# motor.net
KiCad netlist of a schematic drawn in EAGLE
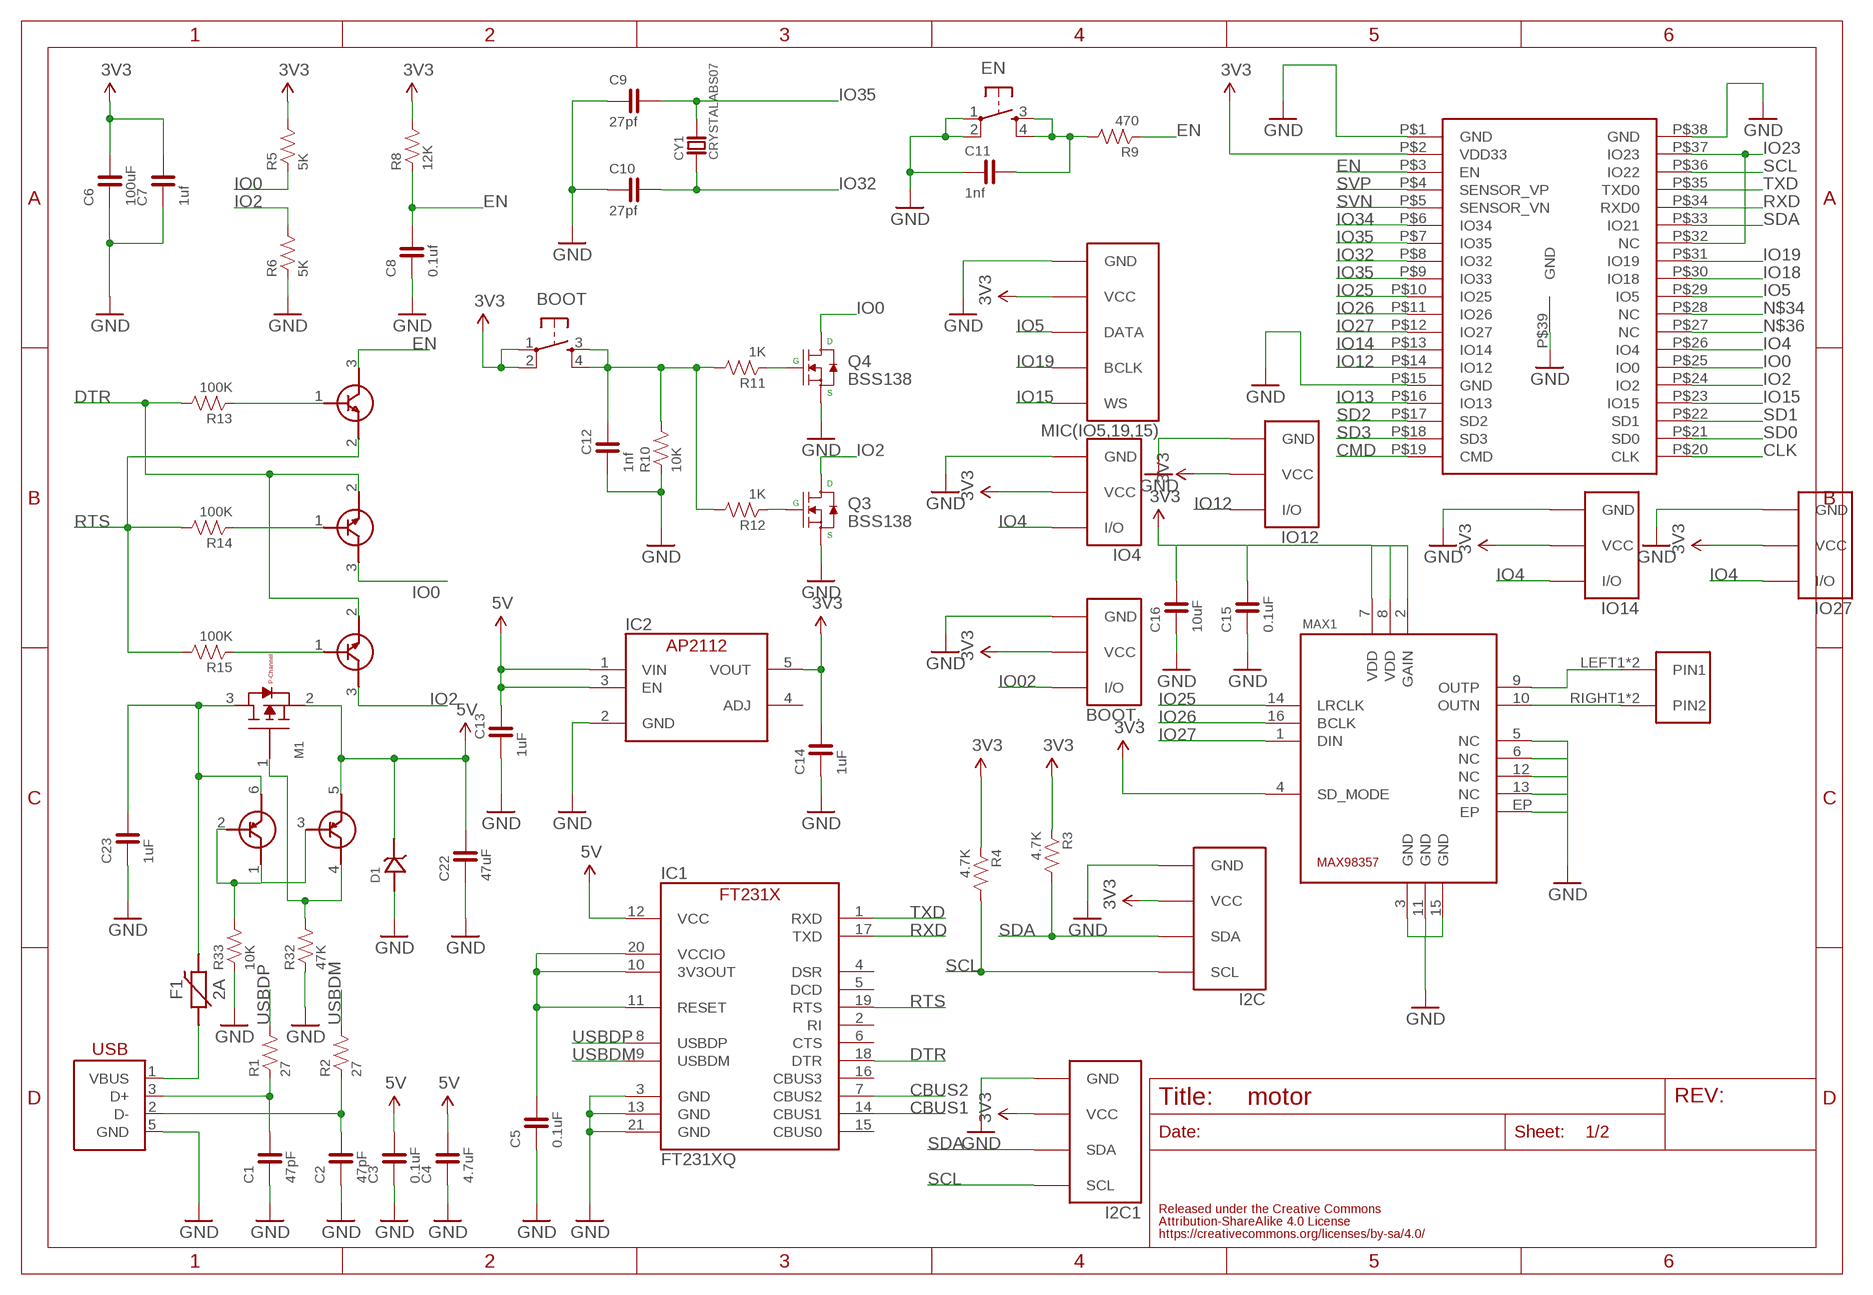
[diagram p0: schematic, sheet 1]
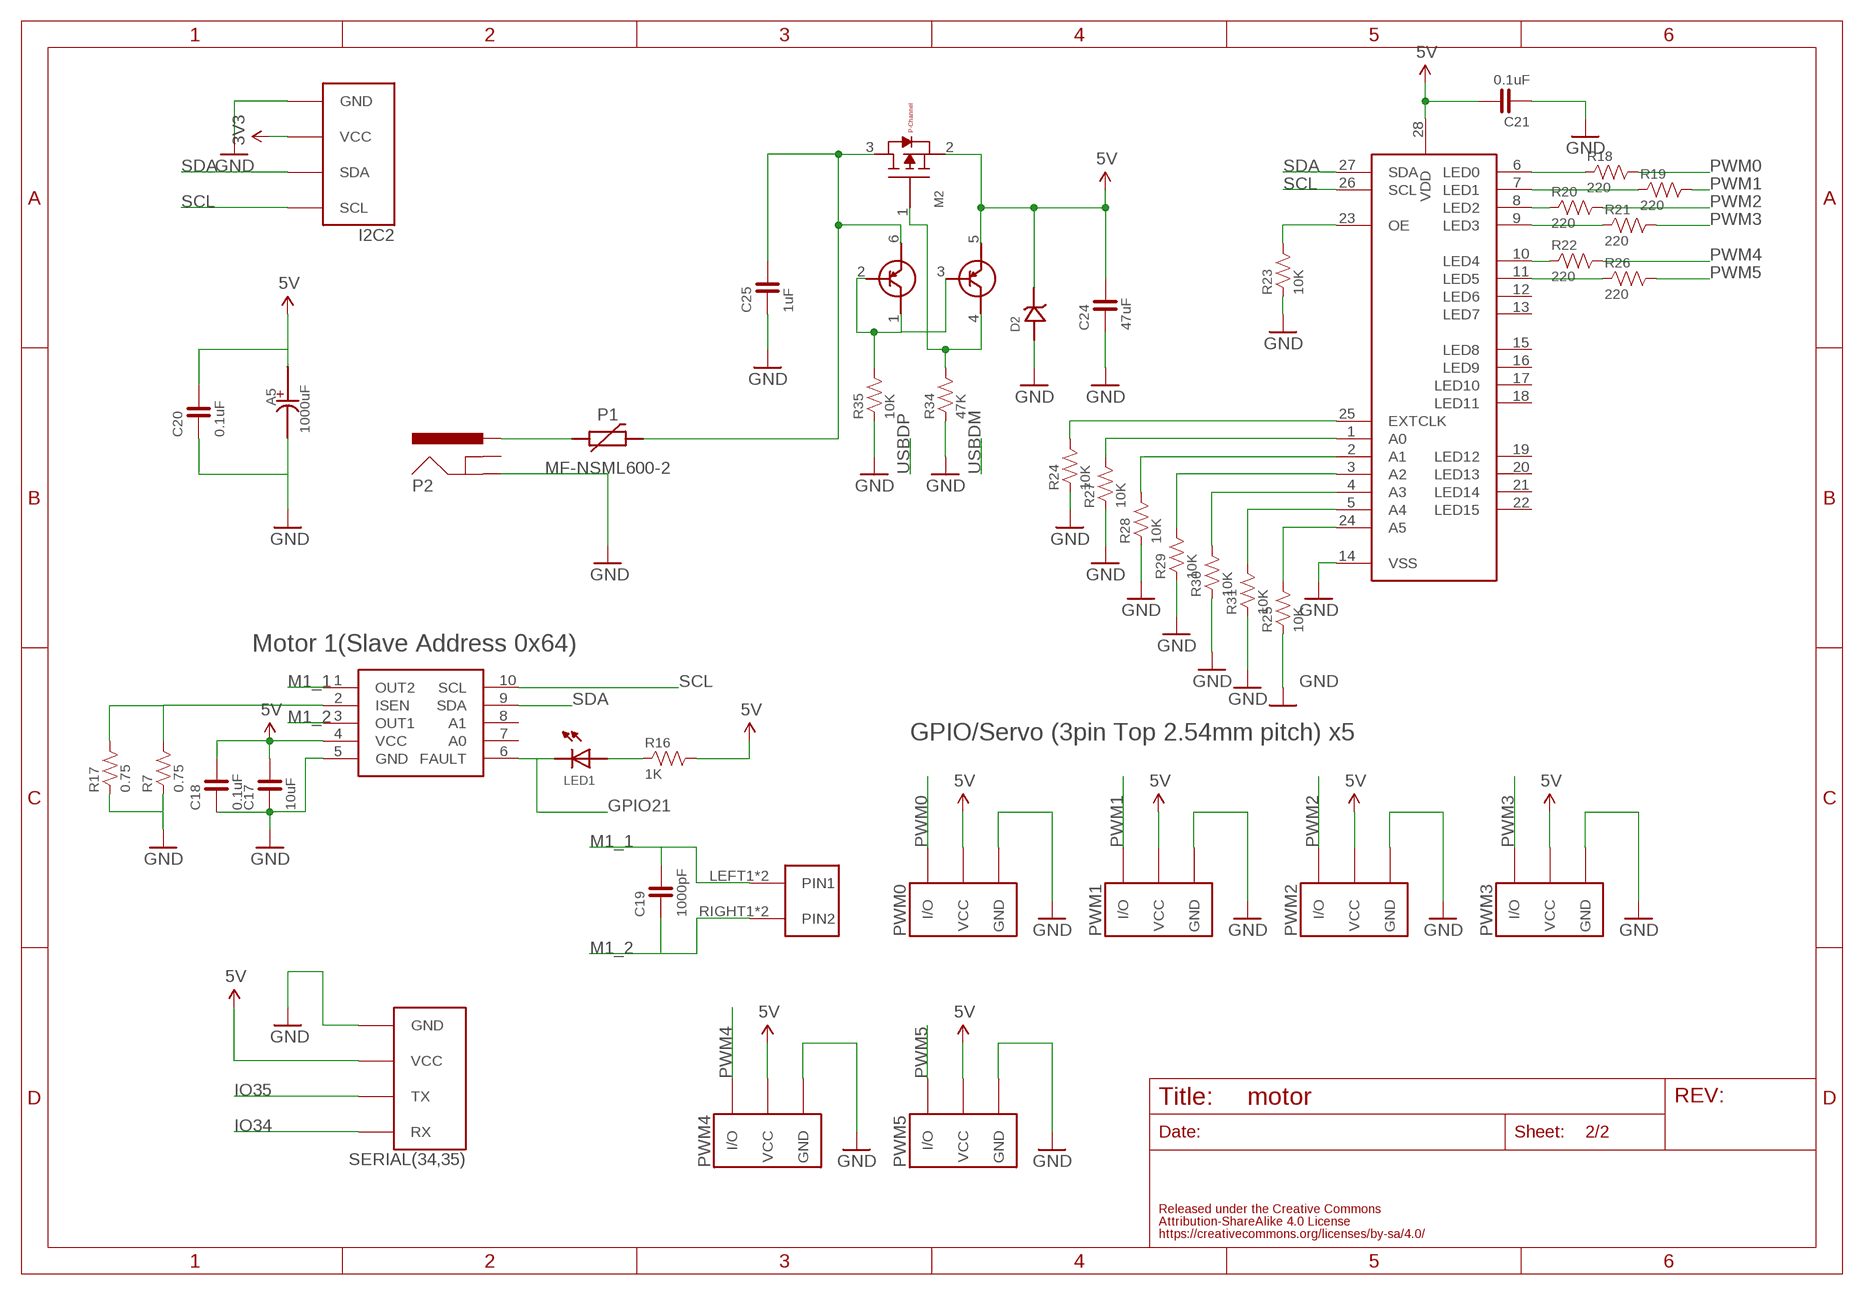
[diagram p1: schematic, sheet 2]

(export (version "E")
  (design (tool "Eeschema 10.0.6"))
  (components
    (comp (ref "A5")
      (value "1000uF")
      (footprint "eagle-import:D12.5")
      (libsource (lib "eagle-import") (part "CAPACITOR-ALUMIN_D12_5"))
    )
    (comp (ref "C17")
      (value "10uF")
      (footprint "eagle-import:0603")
      (libsource (lib "eagle-import") (part "CAPACITOR-0603"))
    )
    (comp (ref "C18")
      (value "0.1uF")
      (footprint "eagle-import:0603")
      (libsource (lib "eagle-import") (part "CAPACITOR-0603"))
    )
    (comp (ref "C19")
      (value "1000pF")
      (footprint "eagle-import:0603")
      (libsource (lib "eagle-import") (part "CAPACITOR-0603"))
    )
    (comp (ref "C20")
      (value "0.1uF")
      (footprint "eagle-import:0603")
      (libsource (lib "eagle-import") (part "CAPACITOR-0603"))
    )
    (comp (ref "C21")
      (value "0.1uF")
      (footprint "eagle-import:0603")
      (libsource (lib "eagle-import") (part "CAPACITOR-0603"))
    )
    (comp (ref "C24")
      (value "47uF")
      (footprint "eagle-import:0603-NARROW")
      (libsource (lib "eagle-import") (part "CAPACITOR-0603_NARROW"))
    )
    (comp (ref "C25")
      (value "1uF")
      (footprint "eagle-import:0603-NARROW")
      (libsource (lib "eagle-import") (part "CAPACITOR-0603_NARROW"))
    )
    (comp (ref "D2")
      (value "SMBJ5.0")
      (footprint "eagle-import:SMBJ5.0")
      (libsource (lib "eagle-import") (part "SMBJ5.0"))
    )
    (comp (ref "I2C2")
      (value "FABO_BRICK_I2C-B04B-PASK-1")
      (footprint "eagle-import:FABO_BRICK_I2C_B04B-PASK-1")
      (libsource (lib "eagle-import") (part "FABO_BRICK_I2C-B04B-PASK-1"))
    )
    (comp (ref "LED1")
      (value "LED-0603")
      (footprint "eagle-import:0603")
      (libsource (lib "eagle-import") (part "LED-0603"))
    )
    (comp (ref "M2")
      (value "MOSFET-P_DMG2305UX")
      (footprint "eagle-import:SOT-23")
      (libsource (lib "eagle-import") (part "MOSFET-P_DMG2305UX"))
    )
    (comp (ref "P1")
      (value "MF-NSML600-2")
      (footprint "eagle-import:1206")
      (libsource (lib "eagle-import") (part "POLYSWITCH1206"))
    )
    (comp (ref "P2")
      (value "DC-JACKM04339A0")
      (footprint "eagle-import:M04339A0")
      (libsource (lib "eagle-import") (part "DC-JACKM04339A0"))
    )
    (comp (ref "PWM0")
      (value "FABO_BRICK_3PIN-HEADER")
      (footprint "eagle-import:FABO_BRICK_3PIN_HEADER")
      (libsource (lib "eagle-import") (part "FABO_BRICK_3PIN-HEADER"))
    )
    (comp (ref "PWM1")
      (value "FABO_BRICK_3PIN-HEADER")
      (footprint "eagle-import:FABO_BRICK_3PIN_HEADER")
      (libsource (lib "eagle-import") (part "FABO_BRICK_3PIN-HEADER"))
    )
    (comp (ref "PWM2")
      (value "FABO_BRICK_3PIN-HEADER")
      (footprint "eagle-import:FABO_BRICK_3PIN_HEADER")
      (libsource (lib "eagle-import") (part "FABO_BRICK_3PIN-HEADER"))
    )
    (comp (ref "PWM3")
      (value "FABO_BRICK_3PIN-HEADER")
      (footprint "eagle-import:FABO_BRICK_3PIN_HEADER")
      (libsource (lib "eagle-import") (part "FABO_BRICK_3PIN-HEADER"))
    )
    (comp (ref "PWM4")
      (value "FABO_BRICK_3PIN-HEADER")
      (footprint "eagle-import:FABO_BRICK_3PIN_HEADER")
      (libsource (lib "eagle-import") (part "FABO_BRICK_3PIN-HEADER"))
    )
    (comp (ref "PWM5")
      (value "FABO_BRICK_3PIN-HEADER")
      (footprint "eagle-import:FABO_BRICK_3PIN_HEADER")
      (libsource (lib "eagle-import") (part "FABO_BRICK_3PIN-HEADER"))
    )
    (comp (ref "R7")
      (value "0.75")
      (footprint "eagle-import:0603")
      (libsource (lib "eagle-import") (part "RESISTOR-0603"))
    )
    (comp (ref "R16")
      (value "1K")
      (footprint "eagle-import:0603")
      (libsource (lib "eagle-import") (part "RESISTOR-0603"))
    )
    (comp (ref "R17")
      (value "0.75")
      (footprint "eagle-import:0603")
      (libsource (lib "eagle-import") (part "RESISTOR-0603"))
    )
    (comp (ref "R18")
      (value "220")
      (footprint "eagle-import:0603")
      (libsource (lib "eagle-import") (part "RESISTOR-0603"))
    )
    (comp (ref "R19")
      (value "220")
      (footprint "eagle-import:0603")
      (libsource (lib "eagle-import") (part "RESISTOR-0603"))
    )
    (comp (ref "R20")
      (value "220")
      (footprint "eagle-import:0603")
      (libsource (lib "eagle-import") (part "RESISTOR-0603"))
    )
    (comp (ref "R21")
      (value "220")
      (footprint "eagle-import:0603")
      (libsource (lib "eagle-import") (part "RESISTOR-0603"))
    )
    (comp (ref "R22")
      (value "220")
      (footprint "eagle-import:0603")
      (libsource (lib "eagle-import") (part "RESISTOR-0603"))
    )
    (comp (ref "R23")
      (value "10K")
      (footprint "eagle-import:0603")
      (libsource (lib "eagle-import") (part "RESISTOR-0603"))
    )
    (comp (ref "R24")
      (value "10K")
      (footprint "eagle-import:0603")
      (libsource (lib "eagle-import") (part "RESISTOR-0603"))
    )
    (comp (ref "R25")
      (value "10K")
      (footprint "eagle-import:0603")
      (libsource (lib "eagle-import") (part "RESISTOR-0603"))
    )
    (comp (ref "R26")
      (value "220")
      (footprint "eagle-import:0603")
      (libsource (lib "eagle-import") (part "RESISTOR-0603"))
    )
    (comp (ref "R27")
      (value "10K")
      (footprint "eagle-import:0603")
      (libsource (lib "eagle-import") (part "RESISTOR-0603"))
    )
    (comp (ref "R28")
      (value "10K")
      (footprint "eagle-import:0603")
      (libsource (lib "eagle-import") (part "RESISTOR-0603"))
    )
    (comp (ref "R29")
      (value "10K")
      (footprint "eagle-import:0603")
      (libsource (lib "eagle-import") (part "RESISTOR-0603"))
    )
    (comp (ref "R30")
      (value "10K")
      (footprint "eagle-import:0603")
      (libsource (lib "eagle-import") (part "RESISTOR-0603"))
    )
    (comp (ref "R31")
      (value "10K")
      (footprint "eagle-import:0603")
      (libsource (lib "eagle-import") (part "RESISTOR-0603"))
    )
    (comp (ref "R34")
      (value "47K")
      (footprint "eagle-import:0603-NARROW")
      (libsource (lib "eagle-import") (part "RESISTOR-0603-NARROW"))
    )
    (comp (ref "R35")
      (value "10K")
      (footprint "eagle-import:0603-NARROW")
      (libsource (lib "eagle-import") (part "RESISTOR-0603-NARROW"))
    )
    (comp (ref "SERIAL(34,35)")
      (value "FABO_BRICK_SERIAL-B04B-PASK-1")
      (footprint "eagle-import:FABO_BRICK_SERIAL_B04B-PASK-1")
      (libsource (lib "eagle-import") (part "FABO_BRICK_SERIAL-B04B-PASK-1"))
    )
    (comp (ref "U$7")
      (value "DUAL-PNP-TRANSISTORDMMT5401")
      (footprint "eagle-import:SOT-26")
      (libsource (lib "eagle-import") (part "DUAL-PNP-TRANSISTORDMMT5401"))
    )
    (comp (ref "U$8")
      (value "DRV8830")
      (footprint "eagle-import:DRV8830")
      (libsource (lib "eagle-import") (part "DRV8830"))
    )
    (comp (ref "U$9")
      (value "PCA9685")
      (footprint "eagle-import:PCA9685")
      (libsource (lib "eagle-import") (part "PCA9685"))
    )
    (comp (ref "U$12")
      (value "ML-1400-S1")
      (footprint "eagle-import:ML-1400-S1")
      (libsource (lib "eagle-import") (part "ML-1400-S1"))
    )
    (comp (ref "BOOT")
      (value "TACT-SWITCH-SMD_KMR2")
      (footprint "eagle-import:KMR2")
      (libsource (lib "eagle-import") (part "TACT-SWITCH-SMD_KMR2"))
    )
    (comp (ref "BOOT.")
      (value "BUTTON")
      (footprint "eagle-import:FABO_BRICK_3PIN_B03B-PASK-1_NAME_BOTTOM")
      (libsource (lib "eagle-import") (part "FABO_BRICK_3PIN-03B-PASK-1_NAME_BOTTOM"))
    )
    (comp (ref "C1")
      (value "47pF")
      (footprint "eagle-import:0603-NARROW")
      (libsource (lib "eagle-import") (part "CAPACITOR-0603_NARROW"))
    )
    (comp (ref "C2")
      (value "47pF")
      (footprint "eagle-import:0603-NARROW")
      (libsource (lib "eagle-import") (part "CAPACITOR-0603_NARROW"))
    )
    (comp (ref "C3")
      (value "0.1uF")
      (footprint "eagle-import:0603-NARROW")
      (libsource (lib "eagle-import") (part "CAPACITOR-0603_NARROW"))
    )
    (comp (ref "C4")
      (value "4.7uF")
      (footprint "eagle-import:0603-NARROW")
      (libsource (lib "eagle-import") (part "CAPACITOR-0603_NARROW"))
    )
    (comp (ref "C5")
      (value "0.1uF")
      (footprint "eagle-import:0603-NARROW")
      (libsource (lib "eagle-import") (part "CAPACITOR-0603_NARROW"))
    )
    (comp (ref "C6")
      (value "100uF")
      (footprint "eagle-import:1206")
      (libsource (lib "eagle-import") (part "CAPACITOR-1206"))
    )
    (comp (ref "C7")
      (value "1uf")
      (footprint "eagle-import:0603-NARROW")
      (libsource (lib "eagle-import") (part "CAPACITOR-0603_NARROW"))
    )
    (comp (ref "C8")
      (value "0.1uf")
      (footprint "eagle-import:0603-NARROW")
      (libsource (lib "eagle-import") (part "CAPACITOR-0603_NARROW"))
    )
    (comp (ref "C9")
      (value "27pf")
      (footprint "eagle-import:0603-NARROW")
      (libsource (lib "eagle-import") (part "CAPACITOR-0603_NARROW"))
    )
    (comp (ref "C10")
      (value "27pf")
      (footprint "eagle-import:0603-NARROW")
      (libsource (lib "eagle-import") (part "CAPACITOR-0603_NARROW"))
    )
    (comp (ref "C11")
      (value "1nf")
      (footprint "eagle-import:0603-NARROW")
      (libsource (lib "eagle-import") (part "CAPACITOR-0603_NARROW"))
    )
    (comp (ref "C12")
      (value "1nf")
      (footprint "eagle-import:0603-NARROW")
      (libsource (lib "eagle-import") (part "CAPACITOR-0603_NARROW"))
    )
    (comp (ref "C13")
      (value "1uF")
      (footprint "eagle-import:0603")
      (libsource (lib "eagle-import") (part "CAPACITOR-0603"))
    )
    (comp (ref "C14")
      (value "1uF")
      (footprint "eagle-import:0603")
      (libsource (lib "eagle-import") (part "CAPACITOR-0603"))
    )
    (comp (ref "C15")
      (value "0.1uF")
      (footprint "eagle-import:0603")
      (libsource (lib "eagle-import") (part "CAPACITOR-0603"))
    )
    (comp (ref "C16")
      (value "10uF")
      (footprint "eagle-import:0603")
      (libsource (lib "eagle-import") (part "CAPACITOR-0603"))
    )
    (comp (ref "C22")
      (value "47uF")
      (footprint "eagle-import:0603-NARROW")
      (libsource (lib "eagle-import") (part "CAPACITOR-0603_NARROW"))
    )
    (comp (ref "C23")
      (value "1uF")
      (footprint "eagle-import:0603-NARROW")
      (libsource (lib "eagle-import") (part "CAPACITOR-0603_NARROW"))
    )
    (comp (ref "CY1")
      (value "CRYSTALABS07")
      (footprint "eagle-import:ABRACOM-ABS07-32.768KHZ")
      (libsource (lib "eagle-import") (part "CRYSTALABS07"))
    )
    (comp (ref "D1")
      (value "SMBJ5.0")
      (footprint "eagle-import:SMBJ5.0")
      (libsource (lib "eagle-import") (part "SMBJ5.0"))
    )
    (comp (ref "EN")
      (value "TACT-SWITCH-SMD_KMR2")
      (footprint "eagle-import:KMR2")
      (libsource (lib "eagle-import") (part "TACT-SWITCH-SMD_KMR2"))
    )
    (comp (ref "F1")
      (value "2A")
      (footprint "eagle-import:NANOSMDC035F")
      (libsource (lib "eagle-import") (part "POLYSWITCH"))
    )
    (comp (ref "I2C")
      (value "FABO_BRICK_I2C-B04B-PASK-1")
      (footprint "eagle-import:FABO_BRICK_I2C_B04B-PASK-1")
      (libsource (lib "eagle-import") (part "FABO_BRICK_I2C-B04B-PASK-1"))
    )
    (comp (ref "I2C1")
      (value "FABO_BRICK_I2C-B04B-PASK-1")
      (footprint "eagle-import:FABO_BRICK_I2C_B04B-PASK-1")
      (libsource (lib "eagle-import") (part "FABO_BRICK_I2C-B04B-PASK-1"))
    )
    (comp (ref "IC1")
      (value "FT231XQ")
      (footprint "eagle-import:QFN-20_FT231X")
      (libsource (lib "eagle-import") (part "FT231XQ"))
    )
    (comp (ref "IC2")
      (value "AP2112K-3.3TRG1")
      (footprint "eagle-import:SOT-23-5")
      (libsource (lib "eagle-import") (part "AP2112K-3.3TRG1"))
    )
    (comp (ref "IO4")
      (value "FABO_BRICK_3PIN-03B-PASK-1_NAME_BOTTOM")
      (footprint "eagle-import:FABO_BRICK_3PIN_B03B-PASK-1_NAME_BOTTOM")
      (libsource (lib "eagle-import") (part "FABO_BRICK_3PIN-03B-PASK-1_NAME_BOTTOM"))
    )
    (comp (ref "IO12")
      (value "FABO_BRICK_3PIN-03B-PASK-1_NAME_BOTTOM")
      (footprint "eagle-import:FABO_BRICK_3PIN_B03B-PASK-1_NAME_BOTTOM")
      (libsource (lib "eagle-import") (part "FABO_BRICK_3PIN-03B-PASK-1_NAME_BOTTOM"))
    )
    (comp (ref "IO14")
      (value "FABO_BRICK_3PIN-03B-PASK-1_NAME_BOTTOM")
      (footprint "eagle-import:FABO_BRICK_3PIN_B03B-PASK-1_NAME_BOTTOM")
      (libsource (lib "eagle-import") (part "FABO_BRICK_3PIN-03B-PASK-1_NAME_BOTTOM"))
    )
    (comp (ref "IO27")
      (value "FABO_BRICK_3PIN-03B-PASK-1_NAME_BOTTOM")
      (footprint "eagle-import:FABO_BRICK_3PIN_B03B-PASK-1_NAME_BOTTOM")
      (libsource (lib "eagle-import") (part "FABO_BRICK_3PIN-03B-PASK-1_NAME_BOTTOM"))
    )
    (comp (ref "M1")
      (value "MOSFET-P_DMG2305UX")
      (footprint "eagle-import:SOT-23")
      (libsource (lib "eagle-import") (part "MOSFET-P_DMG2305UX"))
    )
    (comp (ref "MAX1")
      (value "MA-MAX98357")
      (footprint "eagle-import:MAXIM-MAX98357")
      (libsource (lib "eagle-import") (part "MA-MAX98357"))
    )
    (comp (ref "MIC(IO5,19,15)")
      (value "FABO_BRICK_I2STOP")
      (footprint "eagle-import:FABO_BRICK_I2S_B05B-PARK-1")
      (libsource (lib "eagle-import") (part "FABO_BRICK_I2STOP"))
    )
    (comp (ref "Q3")
      (value "BSS138")
      (footprint "eagle-import:SOT23-3")
      (libsource (lib "eagle-import") (part "MOSFET-N-BSS138"))
    )
    (comp (ref "Q4")
      (value "BSS138")
      (footprint "eagle-import:SOT23-3")
      (libsource (lib "eagle-import") (part "MOSFET-N-BSS138"))
    )
    (comp (ref "R1")
      (value "27")
      (footprint "eagle-import:0603-NARROW")
      (libsource (lib "eagle-import") (part "RESISTOR-0603-NARROW"))
    )
    (comp (ref "R2")
      (value "27")
      (footprint "eagle-import:0603-NARROW")
      (libsource (lib "eagle-import") (part "RESISTOR-0603-NARROW"))
    )
    (comp (ref "R3")
      (value "4.7K")
      (footprint "eagle-import:0603-NARROW")
      (libsource (lib "eagle-import") (part "RESISTOR-0603-NARROW"))
    )
    (comp (ref "R4")
      (value "4.7K")
      (footprint "eagle-import:0603-NARROW")
      (libsource (lib "eagle-import") (part "RESISTOR-0603-NARROW"))
    )
    (comp (ref "R5")
      (value "5K")
      (footprint "eagle-import:0603-NARROW")
      (libsource (lib "eagle-import") (part "RESISTOR-0603-NARROW"))
    )
    (comp (ref "R6")
      (value "5K")
      (footprint "eagle-import:0603-NARROW")
      (libsource (lib "eagle-import") (part "RESISTOR-0603-NARROW"))
    )
    (comp (ref "R8")
      (value "12K")
      (footprint "eagle-import:0603-NARROW")
      (libsource (lib "eagle-import") (part "RESISTOR-0603-NARROW"))
    )
    (comp (ref "R9")
      (value "470")
      (footprint "eagle-import:0603-NARROW")
      (libsource (lib "eagle-import") (part "RESISTOR-0603-NARROW"))
    )
    (comp (ref "R10")
      (value "10K")
      (footprint "eagle-import:0603-NARROW")
      (libsource (lib "eagle-import") (part "RESISTOR-0603-NARROW"))
    )
    (comp (ref "R11")
      (value "1K")
      (footprint "eagle-import:0603-NARROW")
      (libsource (lib "eagle-import") (part "RESISTOR-0603-NARROW"))
    )
    (comp (ref "R12")
      (value "1K")
      (footprint "eagle-import:0603-NARROW")
      (libsource (lib "eagle-import") (part "RESISTOR-0603-NARROW"))
    )
    (comp (ref "R13")
      (value "100K")
      (footprint "eagle-import:0603-NARROW")
      (libsource (lib "eagle-import") (part "RESISTOR-0603-NARROW"))
    )
    (comp (ref "R14")
      (value "100K")
      (footprint "eagle-import:0603-NARROW")
      (libsource (lib "eagle-import") (part "RESISTOR-0603-NARROW"))
    )
    (comp (ref "R15")
      (value "100K")
      (footprint "eagle-import:0603-NARROW")
      (libsource (lib "eagle-import") (part "RESISTOR-0603-NARROW"))
    )
    (comp (ref "R32")
      (value "47K")
      (footprint "eagle-import:0603-NARROW")
      (libsource (lib "eagle-import") (part "RESISTOR-0603-NARROW"))
    )
    (comp (ref "R33")
      (value "10K")
      (footprint "eagle-import:0603-NARROW")
      (libsource (lib "eagle-import") (part "RESISTOR-0603-NARROW"))
    )
    (comp (ref "T1")
      (value "TRANSISTORMMBT2222")
      (footprint "eagle-import:SOT-23")
      (libsource (lib "eagle-import") (part "TRANSISTORMMBT2222"))
    )
    (comp (ref "T2")
      (value "TRANSISTORMMBT2222")
      (footprint "eagle-import:SOT-23")
      (libsource (lib "eagle-import") (part "TRANSISTORMMBT2222"))
    )
    (comp (ref "T3")
      (value "TRANSISTORMMBT2222")
      (footprint "eagle-import:SOT-23")
      (libsource (lib "eagle-import") (part "TRANSISTORMMBT2222"))
    )
    (comp (ref "U$1")
      (value "ESP32-WROVER")
      (footprint "eagle-import:ESP32-WROVER")
      (libsource (lib "eagle-import") (part "ESP32-WROVER"))
    )
    (comp (ref "U$4")
      (value "ML-1400-S1")
      (footprint "eagle-import:ML-1400-S1")
      (libsource (lib "eagle-import") (part "ML-1400-S1"))
    )
    (comp (ref "U$6")
      (value "DUAL-PNP-TRANSISTORDMMT5401")
      (footprint "eagle-import:SOT-26")
      (libsource (lib "eagle-import") (part "DUAL-PNP-TRANSISTORDMMT5401"))
    )
    (comp (ref "USB1")
      (value "USB-MICRO_B_SMT_HIROSE")
      (footprint "eagle-import:ZX62R-B-5P")
      (libsource (lib "eagle-import") (part "USB-MICRO_B_SMT_HIROSE"))
    )
  )
  (nets
    (net (code "1") (name "3V3") (class "Default")
      (node (ref "BOOT") (pin "1") (pinfunction "1_1") (pintype "passive"))
      (node (ref "BOOT") (pin "2") (pinfunction "2_2") (pintype "passive"))
      (node (ref "BOOT.") (pin "VCC") (pinfunction "VCC_VCC") (pintype "bidirectional"))
      (node (ref "C14") (pin "2") (pinfunction "2_2") (pintype "passive"))
      (node (ref "C15") (pin "2") (pinfunction "2_2") (pintype "passive"))
      (node (ref "C16") (pin "2") (pinfunction "2_2") (pintype "passive"))
      (node (ref "C6") (pin "-") (pinfunction "2_-") (pintype "passive"))
      (node (ref "C7") (pin "2") (pinfunction "2_2") (pintype "passive"))
      (node (ref "I2C") (pin "VCC") (pinfunction "VCC_VCC") (pintype "bidirectional"))
      (node (ref "I2C1") (pin "VCC") (pinfunction "VCC_VCC") (pintype "bidirectional"))
      (node (ref "I2C2") (pin "VCC") (pinfunction "VCC_VCC") (pintype "bidirectional"))
      (node (ref "IC2") (pin "5") (pinfunction "VOUT_5") (pintype "bidirectional"))
      (node (ref "IO12") (pin "VCC") (pinfunction "VCC_VCC") (pintype "bidirectional"))
      (node (ref "IO14") (pin "VCC") (pinfunction "VCC_VCC") (pintype "bidirectional"))
      (node (ref "IO27") (pin "VCC") (pinfunction "VCC_VCC") (pintype "bidirectional"))
      (node (ref "IO4") (pin "VCC") (pinfunction "VCC_VCC") (pintype "bidirectional"))
      (node (ref "MAX1") (pin "2") (pinfunction "GAIN_2") (pintype "bidirectional"))
      (node (ref "MAX1") (pin "4") (pinfunction "SD_MODE_4") (pintype "bidirectional"))
      (node (ref "MAX1") (pin "7") (pinfunction "VDD_7") (pintype "bidirectional"))
      (node (ref "MAX1") (pin "8") (pinfunction "VDD_8") (pintype "bidirectional"))
      (node (ref "MIC(IO5,19,15)") (pin "VCC") (pinfunction "VCC_VCC") (pintype "bidirectional"))
      (node (ref "R3") (pin "1") (pinfunction "1_1") (pintype "bidirectional"))
      (node (ref "R4") (pin "1") (pinfunction "1_1") (pintype "bidirectional"))
      (node (ref "R5") (pin "2") (pinfunction "2_2") (pintype "bidirectional"))
      (node (ref "R8") (pin "2") (pinfunction "2_2") (pintype "bidirectional"))
      (node (ref "U$1") (pin "P$2") (pinfunction "VDD33_P$2") (pintype "bidirectional"))
    )
    (net (code "2") (name "5V") (class "Default")
      (node (ref "A5") (pin "+") (pinfunction "+_+") (pintype "passive"))
      (node (ref "C13") (pin "2") (pinfunction "2_2") (pintype "passive"))
      (node (ref "C17") (pin "2") (pinfunction "2_2") (pintype "passive"))
      (node (ref "C18") (pin "2") (pinfunction "2_2") (pintype "passive"))
      (node (ref "C20") (pin "2") (pinfunction "2_2") (pintype "passive"))
      (node (ref "C21") (pin "2") (pinfunction "2_2") (pintype "passive"))
      (node (ref "C22") (pin "2") (pinfunction "2_2") (pintype "passive"))
      (node (ref "C24") (pin "2") (pinfunction "2_2") (pintype "passive"))
      (node (ref "C3") (pin "2") (pinfunction "2_2") (pintype "passive"))
      (node (ref "C4") (pin "2") (pinfunction "2_2") (pintype "passive"))
      (node (ref "D1") (pin "ANODE") (pinfunction "ANODE_ANODE") (pintype "bidirectional"))
      (node (ref "D2") (pin "ANODE") (pinfunction "ANODE_ANODE") (pintype "bidirectional"))
      (node (ref "IC1") (pin "12") (pinfunction "VCC_12") (pintype "bidirectional"))
      (node (ref "IC2") (pin "1") (pinfunction "VIN_1") (pintype "bidirectional"))
      (node (ref "IC2") (pin "3") (pinfunction "EN_3") (pintype "bidirectional"))
      (node (ref "M1") (pin "2") (pinfunction "S_2") (pintype "passive"))
      (node (ref "M2") (pin "2") (pinfunction "S_2") (pintype "passive"))
      (node (ref "PWM0") (pin "VCC") (pinfunction "VCC_VCC") (pintype "bidirectional"))
      (node (ref "PWM1") (pin "VCC") (pinfunction "VCC_VCC") (pintype "bidirectional"))
      (node (ref "PWM2") (pin "VCC") (pinfunction "VCC_VCC") (pintype "bidirectional"))
      (node (ref "PWM3") (pin "VCC") (pinfunction "VCC_VCC") (pintype "bidirectional"))
      (node (ref "PWM4") (pin "VCC") (pinfunction "VCC_VCC") (pintype "bidirectional"))
      (node (ref "PWM5") (pin "VCC") (pinfunction "VCC_VCC") (pintype "bidirectional"))
      (node (ref "R16") (pin "2") (pinfunction "2_2") (pintype "bidirectional"))
      (node (ref "SERIAL(34,35)") (pin "VCC") (pinfunction "VCC_VCC") (pintype "bidirectional"))
      (node (ref "U$6") (pin "5") (pinfunction "E2_5") (pintype "bidirectional"))
      (node (ref "U$7") (pin "5") (pinfunction "E2_5") (pintype "bidirectional"))
      (node (ref "U$8") (pin "4") (pinfunction "VCC_4") (pintype "bidirectional"))
      (node (ref "U$9") (pin "28") (pinfunction "VDD_28") (pintype "bidirectional"))
    )
    (net (code "3") (name "CBUS1") (class "Default")
      (node (ref "IC1") (pin "14") (pinfunction "CBUS1_14") (pintype "bidirectional"))
    )
    (net (code "4") (name "CBUS2") (class "Default")
      (node (ref "IC1") (pin "7") (pinfunction "CBUS2_7") (pintype "bidirectional"))
    )
    (net (code "5") (name "CLK") (class "Default")
      (node (ref "U$1") (pin "P$20") (pinfunction "CLK_P$20") (pintype "bidirectional"))
    )
    (net (code "6") (name "CMD") (class "Default")
      (node (ref "U$1") (pin "P$19") (pinfunction "CMD_P$19") (pintype "bidirectional"))
    )
    (net (code "7") (name "DTR") (class "Default")
      (node (ref "IC1") (pin "18") (pinfunction "DTR_18") (pintype "bidirectional"))
      (node (ref "R13") (pin "2") (pinfunction "2_2") (pintype "bidirectional"))
      (node (ref "T2") (pin "2") (pinfunction "E_2") (pintype "bidirectional"))
      (node (ref "T3") (pin "2") (pinfunction "E_2") (pintype "bidirectional"))
    )
    (net (code "8") (name "EN") (class "Default")
      (node (ref "C8") (pin "2") (pinfunction "2_2") (pintype "passive"))
      (node (ref "R8") (pin "1") (pinfunction "1_1") (pintype "bidirectional"))
      (node (ref "R9") (pin "1") (pinfunction "1_1") (pintype "bidirectional"))
      (node (ref "T1") (pin "3") (pinfunction "C_3") (pintype "bidirectional"))
      (node (ref "U$1") (pin "P$3") (pinfunction "EN_P$3") (pintype "bidirectional"))
    )
    (net (code "9") (name "GND") (class "Default")
      (node (ref "A5") (pin "-") (pinfunction "-_-") (pintype "passive"))
      (node (ref "BOOT.") (pin "GND") (pinfunction "GND_GND") (pintype "bidirectional"))
      (node (ref "C1") (pin "1") (pinfunction "1_1") (pintype "passive"))
      (node (ref "C10") (pin "1") (pinfunction "1_1") (pintype "passive"))
      (node (ref "C11") (pin "1") (pinfunction "1_1") (pintype "passive"))
      (node (ref "C12") (pin "1") (pinfunction "1_1") (pintype "passive"))
      (node (ref "C13") (pin "1") (pinfunction "1_1") (pintype "passive"))
      (node (ref "C14") (pin "1") (pinfunction "1_1") (pintype "passive"))
      (node (ref "C15") (pin "1") (pinfunction "1_1") (pintype "passive"))
      (node (ref "C16") (pin "1") (pinfunction "1_1") (pintype "passive"))
      (node (ref "C17") (pin "1") (pinfunction "1_1") (pintype "passive"))
      (node (ref "C18") (pin "1") (pinfunction "1_1") (pintype "passive"))
      (node (ref "C2") (pin "1") (pinfunction "1_1") (pintype "passive"))
      (node (ref "C20") (pin "1") (pinfunction "1_1") (pintype "passive"))
      (node (ref "C21") (pin "1") (pinfunction "1_1") (pintype "passive"))
      (node (ref "C22") (pin "1") (pinfunction "1_1") (pintype "passive"))
      (node (ref "C23") (pin "1") (pinfunction "1_1") (pintype "passive"))
      (node (ref "C24") (pin "1") (pinfunction "1_1") (pintype "passive"))
      (node (ref "C25") (pin "1") (pinfunction "1_1") (pintype "passive"))
      (node (ref "C3") (pin "1") (pinfunction "1_1") (pintype "passive"))
      (node (ref "C4") (pin "1") (pinfunction "1_1") (pintype "passive"))
      (node (ref "C5") (pin "1") (pinfunction "1_1") (pintype "passive"))
      (node (ref "C6") (pin "+") (pinfunction "1_+") (pintype "passive"))
      (node (ref "C7") (pin "1") (pinfunction "1_1") (pintype "passive"))
      (node (ref "C8") (pin "1") (pinfunction "1_1") (pintype "passive"))
      (node (ref "C9") (pin "1") (pinfunction "1_1") (pintype "passive"))
      (node (ref "D1") (pin "CATHODE") (pinfunction "CATHODE_CATHODE") (pintype "bidirectional"))
      (node (ref "D2") (pin "CATHODE") (pinfunction "CATHODE_CATHODE") (pintype "bidirectional"))
      (node (ref "EN") (pin "1") (pinfunction "1_1") (pintype "passive"))
      (node (ref "EN") (pin "2") (pinfunction "2_2") (pintype "passive"))
      (node (ref "I2C") (pin "GND") (pinfunction "GND_GND") (pintype "bidirectional"))
      (node (ref "I2C1") (pin "GND") (pinfunction "GND_GND") (pintype "bidirectional"))
      (node (ref "I2C2") (pin "GND") (pinfunction "GND_GND") (pintype "bidirectional"))
      (node (ref "IC1") (pin "13") (pinfunction "GND_13") (pintype "bidirectional"))
      (node (ref "IC1") (pin "21") (pinfunction "GND_21") (pintype "bidirectional"))
      (node (ref "IC1") (pin "3") (pinfunction "GND_3") (pintype "bidirectional"))
      (node (ref "IC2") (pin "2") (pinfunction "GND_2") (pintype "bidirectional"))
      (node (ref "IO12") (pin "GND") (pinfunction "GND_GND") (pintype "bidirectional"))
      (node (ref "IO14") (pin "GND") (pinfunction "GND_GND") (pintype "bidirectional"))
      (node (ref "IO27") (pin "GND") (pinfunction "GND_GND") (pintype "bidirectional"))
      (node (ref "IO4") (pin "GND") (pinfunction "GND_GND") (pintype "bidirectional"))
      (node (ref "MAX1") (pin "11") (pinfunction "GND_11") (pintype "bidirectional"))
      (node (ref "MAX1") (pin "12") (pinfunction "NC_12") (pintype "bidirectional"))
      (node (ref "MAX1") (pin "13") (pinfunction "NC_13") (pintype "bidirectional"))
      (node (ref "MAX1") (pin "15") (pinfunction "GND_15") (pintype "bidirectional"))
      (node (ref "MAX1") (pin "3") (pinfunction "GND_3") (pintype "bidirectional"))
      (node (ref "MAX1") (pin "5") (pinfunction "NC_5") (pintype "bidirectional"))
      (node (ref "MAX1") (pin "6") (pinfunction "NC_6") (pintype "bidirectional"))
      (node (ref "MAX1") (pin "EP") (pinfunction "EP_EP") (pintype "bidirectional"))
      (node (ref "MIC(IO5,19,15)") (pin "GND") (pinfunction "GND_GND") (pintype "bidirectional"))
      (node (ref "P2") (pin "GND") (pinfunction "GND_GND") (pintype "bidirectional"))
      (node (ref "PWM0") (pin "GND") (pinfunction "GND_GND") (pintype "bidirectional"))
      (node (ref "PWM1") (pin "GND") (pinfunction "GND_GND") (pintype "bidirectional"))
      (node (ref "PWM2") (pin "GND") (pinfunction "GND_GND") (pintype "bidirectional"))
      (node (ref "PWM3") (pin "GND") (pinfunction "GND_GND") (pintype "bidirectional"))
      (node (ref "PWM4") (pin "GND") (pinfunction "GND_GND") (pintype "bidirectional"))
      (node (ref "PWM5") (pin "GND") (pinfunction "GND_GND") (pintype "bidirectional"))
      (node (ref "Q3") (pin "2") (pinfunction "S_2") (pintype "passive"))
      (node (ref "Q4") (pin "2") (pinfunction "S_2") (pintype "passive"))
      (node (ref "R10") (pin "1") (pinfunction "1_1") (pintype "bidirectional"))
      (node (ref "R17") (pin "1") (pinfunction "1_1") (pintype "bidirectional"))
      (node (ref "R23") (pin "1") (pinfunction "1_1") (pintype "bidirectional"))
      (node (ref "R24") (pin "1") (pinfunction "1_1") (pintype "bidirectional"))
      (node (ref "R25") (pin "1") (pinfunction "1_1") (pintype "bidirectional"))
      (node (ref "R27") (pin "1") (pinfunction "1_1") (pintype "bidirectional"))
      (node (ref "R28") (pin "1") (pinfunction "1_1") (pintype "bidirectional"))
      (node (ref "R29") (pin "1") (pinfunction "1_1") (pintype "bidirectional"))
      (node (ref "R30") (pin "1") (pinfunction "1_1") (pintype "bidirectional"))
      (node (ref "R31") (pin "1") (pinfunction "1_1") (pintype "bidirectional"))
      (node (ref "R32") (pin "1") (pinfunction "1_1") (pintype "bidirectional"))
      (node (ref "R33") (pin "1") (pinfunction "1_1") (pintype "bidirectional"))
      (node (ref "R34") (pin "1") (pinfunction "1_1") (pintype "bidirectional"))
      (node (ref "R35") (pin "1") (pinfunction "1_1") (pintype "bidirectional"))
      (node (ref "R6") (pin "1") (pinfunction "1_1") (pintype "bidirectional"))
      (node (ref "R7") (pin "1") (pinfunction "1_1") (pintype "bidirectional"))
      (node (ref "SERIAL(34,35)") (pin "GND") (pinfunction "GND_GND") (pintype "bidirectional"))
      (node (ref "U$1") (pin "P$1") (pinfunction "GND_P$1") (pintype "bidirectional"))
      (node (ref "U$1") (pin "P$15") (pinfunction "GND_P$15") (pintype "bidirectional"))
      (node (ref "U$1") (pin "P$38") (pinfunction "GND_P$38") (pintype "bidirectional"))
      (node (ref "U$1") (pin "P$39") (pinfunction "GND_P$39") (pintype "bidirectional"))
      (node (ref "U$8") (pin "5") (pinfunction "GND_5") (pintype "bidirectional"))
      (node (ref "U$9") (pin "14") (pinfunction "VSS_14") (pintype "bidirectional"))
      (node (ref "USB1") (pin "5") (pinfunction "GND_5") (pintype "bidirectional"))
    )
    (net (code "10") (name "GPIO21") (class "Default")
      (node (ref "LED1") (pin "CATHODE") (pinfunction "CATHODE_CATHODE") (pintype "passive"))
      (node (ref "U$8") (pin "6") (pinfunction "FAULT_6") (pintype "bidirectional"))
    )
    (net (code "11") (name "IO0") (class "Default")
      (node (ref "Q4") (pin "3") (pinfunction "D_3") (pintype "passive"))
      (node (ref "R5") (pin "1") (pinfunction "1_1") (pintype "bidirectional"))
      (node (ref "T2") (pin "3") (pinfunction "C_3") (pintype "bidirectional"))
      (node (ref "U$1") (pin "P$25") (pinfunction "IO0_P$25") (pintype "bidirectional"))
    )
    (net (code "12") (name "IO02") (class "Default")
      (node (ref "BOOT.") (pin "I/O") (pinfunction "I/O_I/O") (pintype "bidirectional"))
    )
    (net (code "13") (name "IO2") (class "Default")
      (node (ref "Q3") (pin "3") (pinfunction "D_3") (pintype "passive"))
      (node (ref "R6") (pin "2") (pinfunction "2_2") (pintype "bidirectional"))
      (node (ref "T3") (pin "3") (pinfunction "C_3") (pintype "bidirectional"))
      (node (ref "U$1") (pin "P$24") (pinfunction "IO2_P$24") (pintype "bidirectional"))
    )
    (net (code "14") (name "IO4") (class "Default")
      (node (ref "IO14") (pin "I/O") (pinfunction "I/O_I/O") (pintype "bidirectional"))
      (node (ref "IO27") (pin "I/O") (pinfunction "I/O_I/O") (pintype "bidirectional"))
      (node (ref "IO4") (pin "I/O") (pinfunction "I/O_I/O") (pintype "bidirectional"))
      (node (ref "U$1") (pin "P$26") (pinfunction "IO4_P$26") (pintype "bidirectional"))
    )
    (net (code "15") (name "IO5") (class "Default")
      (node (ref "MIC(IO5,19,15)") (pin "DATA") (pinfunction "DATA_DATA") (pintype "bidirectional"))
      (node (ref "U$1") (pin "P$29") (pinfunction "IO5_P$29") (pintype "bidirectional"))
    )
    (net (code "16") (name "IO12") (class "Default")
      (node (ref "IO12") (pin "I/O") (pinfunction "I/O_I/O") (pintype "bidirectional"))
      (node (ref "U$1") (pin "P$14") (pinfunction "IO12_P$14") (pintype "bidirectional"))
    )
    (net (code "17") (name "IO13") (class "Default")
      (node (ref "U$1") (pin "P$16") (pinfunction "IO13_P$16") (pintype "bidirectional"))
    )
    (net (code "18") (name "IO14") (class "Default")
      (node (ref "U$1") (pin "P$13") (pinfunction "IO14_P$13") (pintype "bidirectional"))
    )
    (net (code "19") (name "IO15") (class "Default")
      (node (ref "MIC(IO5,19,15)") (pin "WS") (pinfunction "WS_WS") (pintype "bidirectional"))
      (node (ref "U$1") (pin "P$23") (pinfunction "IO15_P$23") (pintype "bidirectional"))
    )
    (net (code "20") (name "IO18") (class "Default")
      (node (ref "U$1") (pin "P$30") (pinfunction "IO18_P$30") (pintype "bidirectional"))
    )
    (net (code "21") (name "IO19") (class "Default")
      (node (ref "MIC(IO5,19,15)") (pin "BCLK") (pinfunction "BCLK_BCLK") (pintype "bidirectional"))
      (node (ref "U$1") (pin "P$31") (pinfunction "IO19_P$31") (pintype "bidirectional"))
    )
    (net (code "22") (name "IO23") (class "Default")
      (node (ref "U$1") (pin "P$32") (pinfunction "NC_P$32") (pintype "bidirectional"))
      (node (ref "U$1") (pin "P$37") (pinfunction "IO23_P$37") (pintype "bidirectional"))
    )
    (net (code "23") (name "IO25") (class "Default")
      (node (ref "MAX1") (pin "14") (pinfunction "LRCLK_14") (pintype "bidirectional"))
      (node (ref "U$1") (pin "P$10") (pinfunction "IO25_P$10") (pintype "bidirectional"))
    )
    (net (code "24") (name "IO26") (class "Default")
      (node (ref "MAX1") (pin "16") (pinfunction "BCLK_16") (pintype "bidirectional"))
      (node (ref "U$1") (pin "P$11") (pinfunction "IO26_P$11") (pintype "bidirectional"))
    )
    (net (code "25") (name "IO27") (class "Default")
      (node (ref "MAX1") (pin "1") (pinfunction "DIN_1") (pintype "bidirectional"))
      (node (ref "U$1") (pin "P$12") (pinfunction "IO27_P$12") (pintype "bidirectional"))
    )
    (net (code "26") (name "IO32") (class "Default")
      (node (ref "C10") (pin "2") (pinfunction "2_2") (pintype "passive"))
      (node (ref "CY1") (pin "P$1") (pinfunction "P$1_P$1") (pintype "bidirectional"))
      (node (ref "U$1") (pin "P$8") (pinfunction "IO32_P$8") (pintype "bidirectional"))
    )
    (net (code "27") (name "IO34") (class "Default")
      (node (ref "SERIAL(34,35)") (pin "RX") (pinfunction "RX_RX") (pintype "bidirectional"))
      (node (ref "U$1") (pin "P$6") (pinfunction "IO34_P$6") (pintype "bidirectional"))
    )
    (net (code "28") (name "IO35") (class "Default")
      (node (ref "C9") (pin "2") (pinfunction "2_2") (pintype "passive"))
      (node (ref "CY1") (pin "P$2") (pinfunction "P$2_P$2") (pintype "bidirectional"))
      (node (ref "SERIAL(34,35)") (pin "TX") (pinfunction "TX_TX") (pintype "bidirectional"))
      (node (ref "U$1") (pin "P$7") (pinfunction "IO35_P$7") (pintype "bidirectional"))
      (node (ref "U$1") (pin "P$9") (pinfunction "IO33_P$9") (pintype "bidirectional"))
    )
    (net (code "29") (name "M1_1") (class "Default")
      (node (ref "C19") (pin "2") (pinfunction "2_2") (pintype "passive"))
      (node (ref "U$12") (pin "LEFT1") (pinfunction "PIN1_LEFT1") (pintype "bidirectional"))
      (node (ref "U$12") (pin "LEFT2") (pinfunction "PIN1_LEFT2") (pintype "bidirectional"))
      (node (ref "U$8") (pin "1") (pinfunction "OUT2_1") (pintype "bidirectional"))
    )
    (net (code "30") (name "M1_2") (class "Default")
      (node (ref "C19") (pin "1") (pinfunction "1_1") (pintype "passive"))
      (node (ref "U$12") (pin "RIGHT1") (pinfunction "PIN2_RIGHT1") (pintype "bidirectional"))
      (node (ref "U$12") (pin "RIGHT2") (pinfunction "PIN2_RIGHT2") (pintype "bidirectional"))
      (node (ref "U$8") (pin "3") (pinfunction "OUT1_3") (pintype "bidirectional"))
    )
    (net (code "31") (name "N$34") (class "Default")
      (node (ref "U$1") (pin "P$28") (pinfunction "NC_P$28") (pintype "bidirectional"))
    )
    (net (code "32") (name "N$36") (class "Default")
      (node (ref "U$1") (pin "P$27") (pinfunction "NC_P$27") (pintype "bidirectional"))
    )
    (net (code "33") (name "Net-(BOOT-Pad3)") (class "Default")
      (node (ref "BOOT") (pin "3") (pinfunction "3_3") (pintype "passive"))
      (node (ref "BOOT") (pin "4") (pinfunction "4_4") (pintype "passive"))
      (node (ref "C12") (pin "2") (pinfunction "2_2") (pintype "passive"))
      (node (ref "R10") (pin "2") (pinfunction "2_2") (pintype "bidirectional"))
      (node (ref "R11") (pin "2") (pinfunction "2_2") (pintype "bidirectional"))
      (node (ref "R12") (pin "2") (pinfunction "2_2") (pintype "bidirectional"))
    )
    (net (code "34") (name "Net-(C11-Pad2)") (class "Default")
      (node (ref "C11") (pin "2") (pinfunction "2_2") (pintype "passive"))
      (node (ref "EN") (pin "3") (pinfunction "3_3") (pintype "passive"))
      (node (ref "EN") (pin "4") (pinfunction "4_4") (pintype "passive"))
      (node (ref "R9") (pin "2") (pinfunction "2_2") (pintype "bidirectional"))
    )
    (net (code "35") (name "Net-(IC1-3V3OUT)") (class "Default")
      (node (ref "C5") (pin "2") (pinfunction "2_2") (pintype "passive"))
      (node (ref "IC1") (pin "10") (pinfunction "3V3OUT_10") (pintype "bidirectional"))
      (node (ref "IC1") (pin "11") (pinfunction "RESET_11") (pintype "bidirectional"))
      (node (ref "IC1") (pin "20") (pinfunction "VCCIO_20") (pintype "bidirectional"))
    )
    (net (code "36") (name "Net-(LED1-PadANODE)") (class "Default")
      (node (ref "LED1") (pin "ANODE") (pinfunction "ANODE_ANODE") (pintype "passive"))
      (node (ref "R16") (pin "1") (pinfunction "1_1") (pintype "bidirectional"))
    )
    (net (code "37") (name "Net-(M1-D)") (class "Default")
      (node (ref "C23") (pin "2") (pinfunction "2_2") (pintype "passive"))
      (node (ref "F1") (pin "2") (pinfunction "2_2") (pintype "bidirectional"))
      (node (ref "M1") (pin "3") (pinfunction "D_3") (pintype "passive"))
      (node (ref "U$6") (pin "6") (pinfunction "E1_6") (pintype "bidirectional"))
    )
    (net (code "38") (name "Net-(M1-G)") (class "Default")
      (node (ref "M1") (pin "1") (pinfunction "G_1") (pintype "passive"))
      (node (ref "R32") (pin "2") (pinfunction "2_2") (pintype "bidirectional"))
      (node (ref "U$6") (pin "4") (pinfunction "C2_4") (pintype "bidirectional"))
    )
    (net (code "39") (name "Net-(M2-D)") (class "Default")
      (node (ref "C25") (pin "2") (pinfunction "2_2") (pintype "passive"))
      (node (ref "M2") (pin "3") (pinfunction "D_3") (pintype "passive"))
      (node (ref "P1") (pin "P$2") (pinfunction "2_P$2") (pintype "bidirectional"))
      (node (ref "U$7") (pin "6") (pinfunction "E1_6") (pintype "bidirectional"))
    )
    (net (code "40") (name "Net-(M2-G)") (class "Default")
      (node (ref "M2") (pin "1") (pinfunction "G_1") (pintype "passive"))
      (node (ref "R34") (pin "2") (pinfunction "2_2") (pintype "bidirectional"))
      (node (ref "U$7") (pin "4") (pinfunction "C2_4") (pintype "bidirectional"))
    )
    (net (code "41") (name "Net-(MAX1-OUTN)") (class "Default")
      (node (ref "MAX1") (pin "10") (pinfunction "OUTN_10") (pintype "bidirectional"))
      (node (ref "U$4") (pin "RIGHT1") (pinfunction "PIN2_RIGHT1") (pintype "bidirectional"))
      (node (ref "U$4") (pin "RIGHT2") (pinfunction "PIN2_RIGHT2") (pintype "bidirectional"))
    )
    (net (code "42") (name "Net-(MAX1-OUTP)") (class "Default")
      (node (ref "MAX1") (pin "9") (pinfunction "OUTP_9") (pintype "bidirectional"))
      (node (ref "U$4") (pin "LEFT1") (pinfunction "PIN1_LEFT1") (pintype "bidirectional"))
      (node (ref "U$4") (pin "LEFT2") (pinfunction "PIN1_LEFT2") (pintype "bidirectional"))
    )
    (net (code "43") (name "Net-(P1-1)") (class "Default")
      (node (ref "P1") (pin "P$1") (pinfunction "1_P$1") (pintype "bidirectional"))
      (node (ref "P2") (pin "VCC") (pinfunction "PWR_VCC") (pintype "bidirectional"))
    )
    (net (code "44") (name "Net-(Q3-G)") (class "Default")
      (node (ref "Q3") (pin "1") (pinfunction "G_1") (pintype "passive"))
      (node (ref "R12") (pin "1") (pinfunction "1_1") (pintype "bidirectional"))
    )
    (net (code "45") (name "Net-(Q4-G)") (class "Default")
      (node (ref "Q4") (pin "1") (pinfunction "G_1") (pintype "passive"))
      (node (ref "R11") (pin "1") (pinfunction "1_1") (pintype "bidirectional"))
    )
    (net (code "46") (name "Net-(T1-B)") (class "Default")
      (node (ref "R13") (pin "1") (pinfunction "1_1") (pintype "bidirectional"))
      (node (ref "T1") (pin "1") (pinfunction "B_1") (pintype "bidirectional"))
    )
    (net (code "47") (name "Net-(T2-B)") (class "Default")
      (node (ref "R14") (pin "1") (pinfunction "1_1") (pintype "bidirectional"))
      (node (ref "T2") (pin "1") (pinfunction "B_1") (pintype "bidirectional"))
    )
    (net (code "48") (name "Net-(T3-B)") (class "Default")
      (node (ref "R15") (pin "1") (pinfunction "1_1") (pintype "bidirectional"))
      (node (ref "T3") (pin "1") (pinfunction "B_1") (pintype "bidirectional"))
    )
    (net (code "49") (name "Net-(U$6-B1)") (class "Default")
      (node (ref "R33") (pin "2") (pinfunction "2_2") (pintype "bidirectional"))
      (node (ref "U$6") (pin "1") (pinfunction "C1_1") (pintype "bidirectional"))
      (node (ref "U$6") (pin "2") (pinfunction "B1_2") (pintype "bidirectional"))
      (node (ref "U$6") (pin "3") (pinfunction "B2_3") (pintype "bidirectional"))
    )
    (net (code "50") (name "Net-(U$7-B1)") (class "Default")
      (node (ref "R35") (pin "2") (pinfunction "2_2") (pintype "bidirectional"))
      (node (ref "U$7") (pin "1") (pinfunction "C1_1") (pintype "bidirectional"))
      (node (ref "U$7") (pin "2") (pinfunction "B1_2") (pintype "bidirectional"))
      (node (ref "U$7") (pin "3") (pinfunction "B2_3") (pintype "bidirectional"))
    )
    (net (code "51") (name "Net-(U$8-ISEN)") (class "Default")
      (node (ref "R17") (pin "2") (pinfunction "2_2") (pintype "bidirectional"))
      (node (ref "R7") (pin "2") (pinfunction "2_2") (pintype "bidirectional"))
      (node (ref "U$8") (pin "2") (pinfunction "ISEN_2") (pintype "bidirectional"))
    )
    (net (code "52") (name "Net-(U$9-A0)") (class "Default")
      (node (ref "R27") (pin "2") (pinfunction "2_2") (pintype "bidirectional"))
      (node (ref "U$9") (pin "1") (pinfunction "A0_1") (pintype "bidirectional"))
    )
    (net (code "53") (name "Net-(U$9-A1)") (class "Default")
      (node (ref "R28") (pin "2") (pinfunction "2_2") (pintype "bidirectional"))
      (node (ref "U$9") (pin "2") (pinfunction "A1_2") (pintype "bidirectional"))
    )
    (net (code "54") (name "Net-(U$9-A2)") (class "Default")
      (node (ref "R29") (pin "2") (pinfunction "2_2") (pintype "bidirectional"))
      (node (ref "U$9") (pin "3") (pinfunction "A2_3") (pintype "bidirectional"))
    )
    (net (code "55") (name "Net-(U$9-A3)") (class "Default")
      (node (ref "R30") (pin "2") (pinfunction "2_2") (pintype "bidirectional"))
      (node (ref "U$9") (pin "4") (pinfunction "A3_4") (pintype "bidirectional"))
    )
    (net (code "56") (name "Net-(U$9-A4)") (class "Default")
      (node (ref "R31") (pin "2") (pinfunction "2_2") (pintype "bidirectional"))
      (node (ref "U$9") (pin "5") (pinfunction "A4_5") (pintype "bidirectional"))
    )
    (net (code "57") (name "Net-(U$9-A5)") (class "Default")
      (node (ref "R25") (pin "2") (pinfunction "2_2") (pintype "bidirectional"))
      (node (ref "U$9") (pin "24") (pinfunction "A5_24") (pintype "bidirectional"))
    )
    (net (code "58") (name "Net-(U$9-EXTCLK)") (class "Default")
      (node (ref "R24") (pin "2") (pinfunction "2_2") (pintype "bidirectional"))
      (node (ref "U$9") (pin "25") (pinfunction "EXTCLK_25") (pintype "bidirectional"))
    )
    (net (code "59") (name "Net-(U$9-LED0)") (class "Default")
      (node (ref "R18") (pin "1") (pinfunction "1_1") (pintype "bidirectional"))
      (node (ref "U$9") (pin "6") (pinfunction "LED0_6") (pintype "bidirectional"))
    )
    (net (code "60") (name "Net-(U$9-LED1)") (class "Default")
      (node (ref "R19") (pin "1") (pinfunction "1_1") (pintype "bidirectional"))
      (node (ref "U$9") (pin "7") (pinfunction "LED1_7") (pintype "bidirectional"))
    )
    (net (code "61") (name "Net-(U$9-LED2)") (class "Default")
      (node (ref "R20") (pin "1") (pinfunction "1_1") (pintype "bidirectional"))
      (node (ref "U$9") (pin "8") (pinfunction "LED2_8") (pintype "bidirectional"))
    )
    (net (code "62") (name "Net-(U$9-LED3)") (class "Default")
      (node (ref "R21") (pin "1") (pinfunction "1_1") (pintype "bidirectional"))
      (node (ref "U$9") (pin "9") (pinfunction "LED3_9") (pintype "bidirectional"))
    )
    (net (code "63") (name "Net-(U$9-LED4)") (class "Default")
      (node (ref "R22") (pin "1") (pinfunction "1_1") (pintype "bidirectional"))
      (node (ref "U$9") (pin "10") (pinfunction "LED4_10") (pintype "bidirectional"))
    )
    (net (code "64") (name "Net-(U$9-LED5)") (class "Default")
      (node (ref "R26") (pin "1") (pinfunction "1_1") (pintype "bidirectional"))
      (node (ref "U$9") (pin "11") (pinfunction "LED5_11") (pintype "bidirectional"))
    )
    (net (code "65") (name "Net-(U$9-OE)") (class "Default")
      (node (ref "R23") (pin "2") (pinfunction "2_2") (pintype "bidirectional"))
      (node (ref "U$9") (pin "23") (pinfunction "OE_23") (pintype "bidirectional"))
    )
    (net (code "66") (name "Net-(USB1-D+)") (class "Default")
      (node (ref "C1") (pin "2") (pinfunction "2_2") (pintype "passive"))
      (node (ref "R1") (pin "1") (pinfunction "1_1") (pintype "bidirectional"))
      (node (ref "USB1") (pin "3") (pinfunction "D+_3") (pintype "bidirectional"))
    )
    (net (code "67") (name "Net-(USB1-D-)") (class "Default")
      (node (ref "C2") (pin "2") (pinfunction "2_2") (pintype "passive"))
      (node (ref "R2") (pin "1") (pinfunction "1_1") (pintype "bidirectional"))
      (node (ref "USB1") (pin "2") (pinfunction "D-_2") (pintype "bidirectional"))
    )
    (net (code "68") (name "Net-(USB1-VBUS)") (class "Default")
      (node (ref "F1") (pin "1") (pinfunction "1_1") (pintype "bidirectional"))
      (node (ref "USB1") (pin "1") (pinfunction "VBUS_1") (pintype "bidirectional"))
    )
    (net (code "69") (name "PWM0") (class "Default")
      (node (ref "PWM0") (pin "I/O") (pinfunction "I/O_I/O") (pintype "bidirectional"))
      (node (ref "R18") (pin "2") (pinfunction "2_2") (pintype "bidirectional"))
    )
    (net (code "70") (name "PWM1") (class "Default")
      (node (ref "PWM1") (pin "I/O") (pinfunction "I/O_I/O") (pintype "bidirectional"))
      (node (ref "R19") (pin "2") (pinfunction "2_2") (pintype "bidirectional"))
    )
    (net (code "71") (name "PWM2") (class "Default")
      (node (ref "PWM2") (pin "I/O") (pinfunction "I/O_I/O") (pintype "bidirectional"))
      (node (ref "R20") (pin "2") (pinfunction "2_2") (pintype "bidirectional"))
    )
    (net (code "72") (name "PWM3") (class "Default")
      (node (ref "PWM3") (pin "I/O") (pinfunction "I/O_I/O") (pintype "bidirectional"))
      (node (ref "R21") (pin "2") (pinfunction "2_2") (pintype "bidirectional"))
    )
    (net (code "73") (name "PWM4") (class "Default")
      (node (ref "PWM4") (pin "I/O") (pinfunction "I/O_I/O") (pintype "bidirectional"))
      (node (ref "R22") (pin "2") (pinfunction "2_2") (pintype "bidirectional"))
    )
    (net (code "74") (name "PWM5") (class "Default")
      (node (ref "PWM5") (pin "I/O") (pinfunction "I/O_I/O") (pintype "bidirectional"))
      (node (ref "R26") (pin "2") (pinfunction "2_2") (pintype "bidirectional"))
    )
    (net (code "75") (name "RTS") (class "Default")
      (node (ref "IC1") (pin "19") (pinfunction "RTS_19") (pintype "bidirectional"))
      (node (ref "R14") (pin "2") (pinfunction "2_2") (pintype "bidirectional"))
      (node (ref "R15") (pin "2") (pinfunction "2_2") (pintype "bidirectional"))
      (node (ref "T1") (pin "2") (pinfunction "E_2") (pintype "bidirectional"))
    )
    (net (code "76") (name "RXD") (class "Default")
      (node (ref "IC1") (pin "17") (pinfunction "TXD_17") (pintype "bidirectional"))
      (node (ref "U$1") (pin "P$34") (pinfunction "RXD0_P$34") (pintype "bidirectional"))
    )
    (net (code "77") (name "SCL") (class "Default")
      (node (ref "I2C") (pin "SCL") (pinfunction "SCL_SCL") (pintype "bidirectional"))
      (node (ref "I2C1") (pin "SCL") (pinfunction "SCL_SCL") (pintype "bidirectional"))
      (node (ref "I2C2") (pin "SCL") (pinfunction "SCL_SCL") (pintype "bidirectional"))
      (node (ref "R4") (pin "2") (pinfunction "2_2") (pintype "bidirectional"))
      (node (ref "U$1") (pin "P$36") (pinfunction "IO22_P$36") (pintype "bidirectional"))
      (node (ref "U$8") (pin "10") (pinfunction "SCL_10") (pintype "bidirectional"))
      (node (ref "U$9") (pin "26") (pinfunction "SCL_26") (pintype "bidirectional"))
    )
    (net (code "78") (name "SD0") (class "Default")
      (node (ref "U$1") (pin "P$21") (pinfunction "SD0_P$21") (pintype "bidirectional"))
    )
    (net (code "79") (name "SD1") (class "Default")
      (node (ref "U$1") (pin "P$22") (pinfunction "SD1_P$22") (pintype "bidirectional"))
    )
    (net (code "80") (name "SD2") (class "Default")
      (node (ref "U$1") (pin "P$17") (pinfunction "SD2_P$17") (pintype "bidirectional"))
    )
    (net (code "81") (name "SD3") (class "Default")
      (node (ref "U$1") (pin "P$18") (pinfunction "SD3_P$18") (pintype "bidirectional"))
    )
    (net (code "82") (name "SDA") (class "Default")
      (node (ref "I2C") (pin "SDA") (pinfunction "SDA_SDA") (pintype "bidirectional"))
      (node (ref "I2C1") (pin "SDA") (pinfunction "SDA_SDA") (pintype "bidirectional"))
      (node (ref "I2C2") (pin "SDA") (pinfunction "SDA_SDA") (pintype "bidirectional"))
      (node (ref "R3") (pin "2") (pinfunction "2_2") (pintype "bidirectional"))
      (node (ref "U$1") (pin "P$33") (pinfunction "IO21_P$33") (pintype "bidirectional"))
      (node (ref "U$8") (pin "9") (pinfunction "SDA_9") (pintype "bidirectional"))
      (node (ref "U$9") (pin "27") (pinfunction "SDA_27") (pintype "bidirectional"))
    )
    (net (code "83") (name "SVN") (class "Default")
      (node (ref "U$1") (pin "P$5") (pinfunction "SENSOR_VN_P$5") (pintype "bidirectional"))
    )
    (net (code "84") (name "SVP") (class "Default")
      (node (ref "U$1") (pin "P$4") (pinfunction "SENSOR_VP_P$4") (pintype "bidirectional"))
    )
    (net (code "85") (name "TXD") (class "Default")
      (node (ref "IC1") (pin "1") (pinfunction "RXD_1") (pintype "bidirectional"))
      (node (ref "U$1") (pin "P$35") (pinfunction "TXD0_P$35") (pintype "bidirectional"))
    )
    (net (code "86") (name "USBDM") (class "Default")
      (node (ref "IC1") (pin "9") (pinfunction "USBDM_9") (pintype "bidirectional"))
      (node (ref "R2") (pin "2") (pinfunction "2_2") (pintype "bidirectional"))
    )
    (net (code "87") (name "USBDP") (class "Default")
      (node (ref "IC1") (pin "8") (pinfunction "USBDP_8") (pintype "bidirectional"))
      (node (ref "R1") (pin "2") (pinfunction "2_2") (pintype "bidirectional"))
    )
    (net (code "88") (name "unconnected-(IC1-CBUS0-Pad15)") (class "Default")
      (node (ref "IC1") (pin "15") (pinfunction "CBUS0_15") (pintype "bidirectional"))
    )
    (net (code "89") (name "unconnected-(IC1-CBUS3-Pad16)") (class "Default")
      (node (ref "IC1") (pin "16") (pinfunction "CBUS3_16") (pintype "bidirectional"))
    )
    (net (code "90") (name "unconnected-(IC1-CTS-Pad6)") (class "Default")
      (node (ref "IC1") (pin "6") (pinfunction "CTS_6") (pintype "bidirectional"))
    )
    (net (code "91") (name "unconnected-(IC1-DCD-Pad5)") (class "Default")
      (node (ref "IC1") (pin "5") (pinfunction "DCD_5") (pintype "bidirectional"))
    )
    (net (code "92") (name "unconnected-(IC1-DSR-Pad4)") (class "Default")
      (node (ref "IC1") (pin "4") (pinfunction "DSR_4") (pintype "bidirectional"))
    )
    (net (code "93") (name "unconnected-(IC1-RI-Pad2)") (class "Default")
      (node (ref "IC1") (pin "2") (pinfunction "RI_2") (pintype "bidirectional"))
    )
    (net (code "94") (name "unconnected-(IC2-ADJ-Pad4)") (class "Default")
      (node (ref "IC2") (pin "4") (pinfunction "ADJ_4") (pintype "bidirectional"))
    )
    (net (code "95") (name "unconnected-(P2-PadGNDBREAK)") (class "Default")
      (node (ref "P2") (pin "GNDBREAK") (pinfunction "GNDBREAK_GNDBREAK") (pintype "bidirectional"))
    )
    (net (code "96") (name "unconnected-(U$8-A0-Pad7)") (class "Default")
      (node (ref "U$8") (pin "7") (pinfunction "A0_7") (pintype "bidirectional"))
    )
    (net (code "97") (name "unconnected-(U$8-A1-Pad8)") (class "Default")
      (node (ref "U$8") (pin "8") (pinfunction "A1_8") (pintype "bidirectional"))
    )
    (net (code "98") (name "unconnected-(U$9-LED6-Pad12)") (class "Default")
      (node (ref "U$9") (pin "12") (pinfunction "LED6_12") (pintype "bidirectional"))
    )
    (net (code "99") (name "unconnected-(U$9-LED7-Pad13)") (class "Default")
      (node (ref "U$9") (pin "13") (pinfunction "LED7_13") (pintype "bidirectional"))
    )
    (net (code "100") (name "unconnected-(U$9-LED8-Pad15)") (class "Default")
      (node (ref "U$9") (pin "15") (pinfunction "LED8_15") (pintype "bidirectional"))
    )
    (net (code "101") (name "unconnected-(U$9-LED9-Pad16)") (class "Default")
      (node (ref "U$9") (pin "16") (pinfunction "LED9_16") (pintype "bidirectional"))
    )
    (net (code "102") (name "unconnected-(U$9-LED10-Pad17)") (class "Default")
      (node (ref "U$9") (pin "17") (pinfunction "LED10_17") (pintype "bidirectional"))
    )
    (net (code "103") (name "unconnected-(U$9-LED11-Pad18)") (class "Default")
      (node (ref "U$9") (pin "18") (pinfunction "LED11_18") (pintype "bidirectional"))
    )
    (net (code "104") (name "unconnected-(U$9-LED12-Pad19)") (class "Default")
      (node (ref "U$9") (pin "19") (pinfunction "LED12_19") (pintype "bidirectional"))
    )
    (net (code "105") (name "unconnected-(U$9-LED13-Pad20)") (class "Default")
      (node (ref "U$9") (pin "20") (pinfunction "LED13_20") (pintype "bidirectional"))
    )
    (net (code "106") (name "unconnected-(U$9-LED14-Pad21)") (class "Default")
      (node (ref "U$9") (pin "21") (pinfunction "LED14_21") (pintype "bidirectional"))
    )
    (net (code "107") (name "unconnected-(U$9-LED15-Pad22)") (class "Default")
      (node (ref "U$9") (pin "22") (pinfunction "LED15_22") (pintype "bidirectional"))
    )
  )
)
